# ROM-BANK_004_EAGLE_630.net
KiCad netlist of a schematic drawn in EAGLE
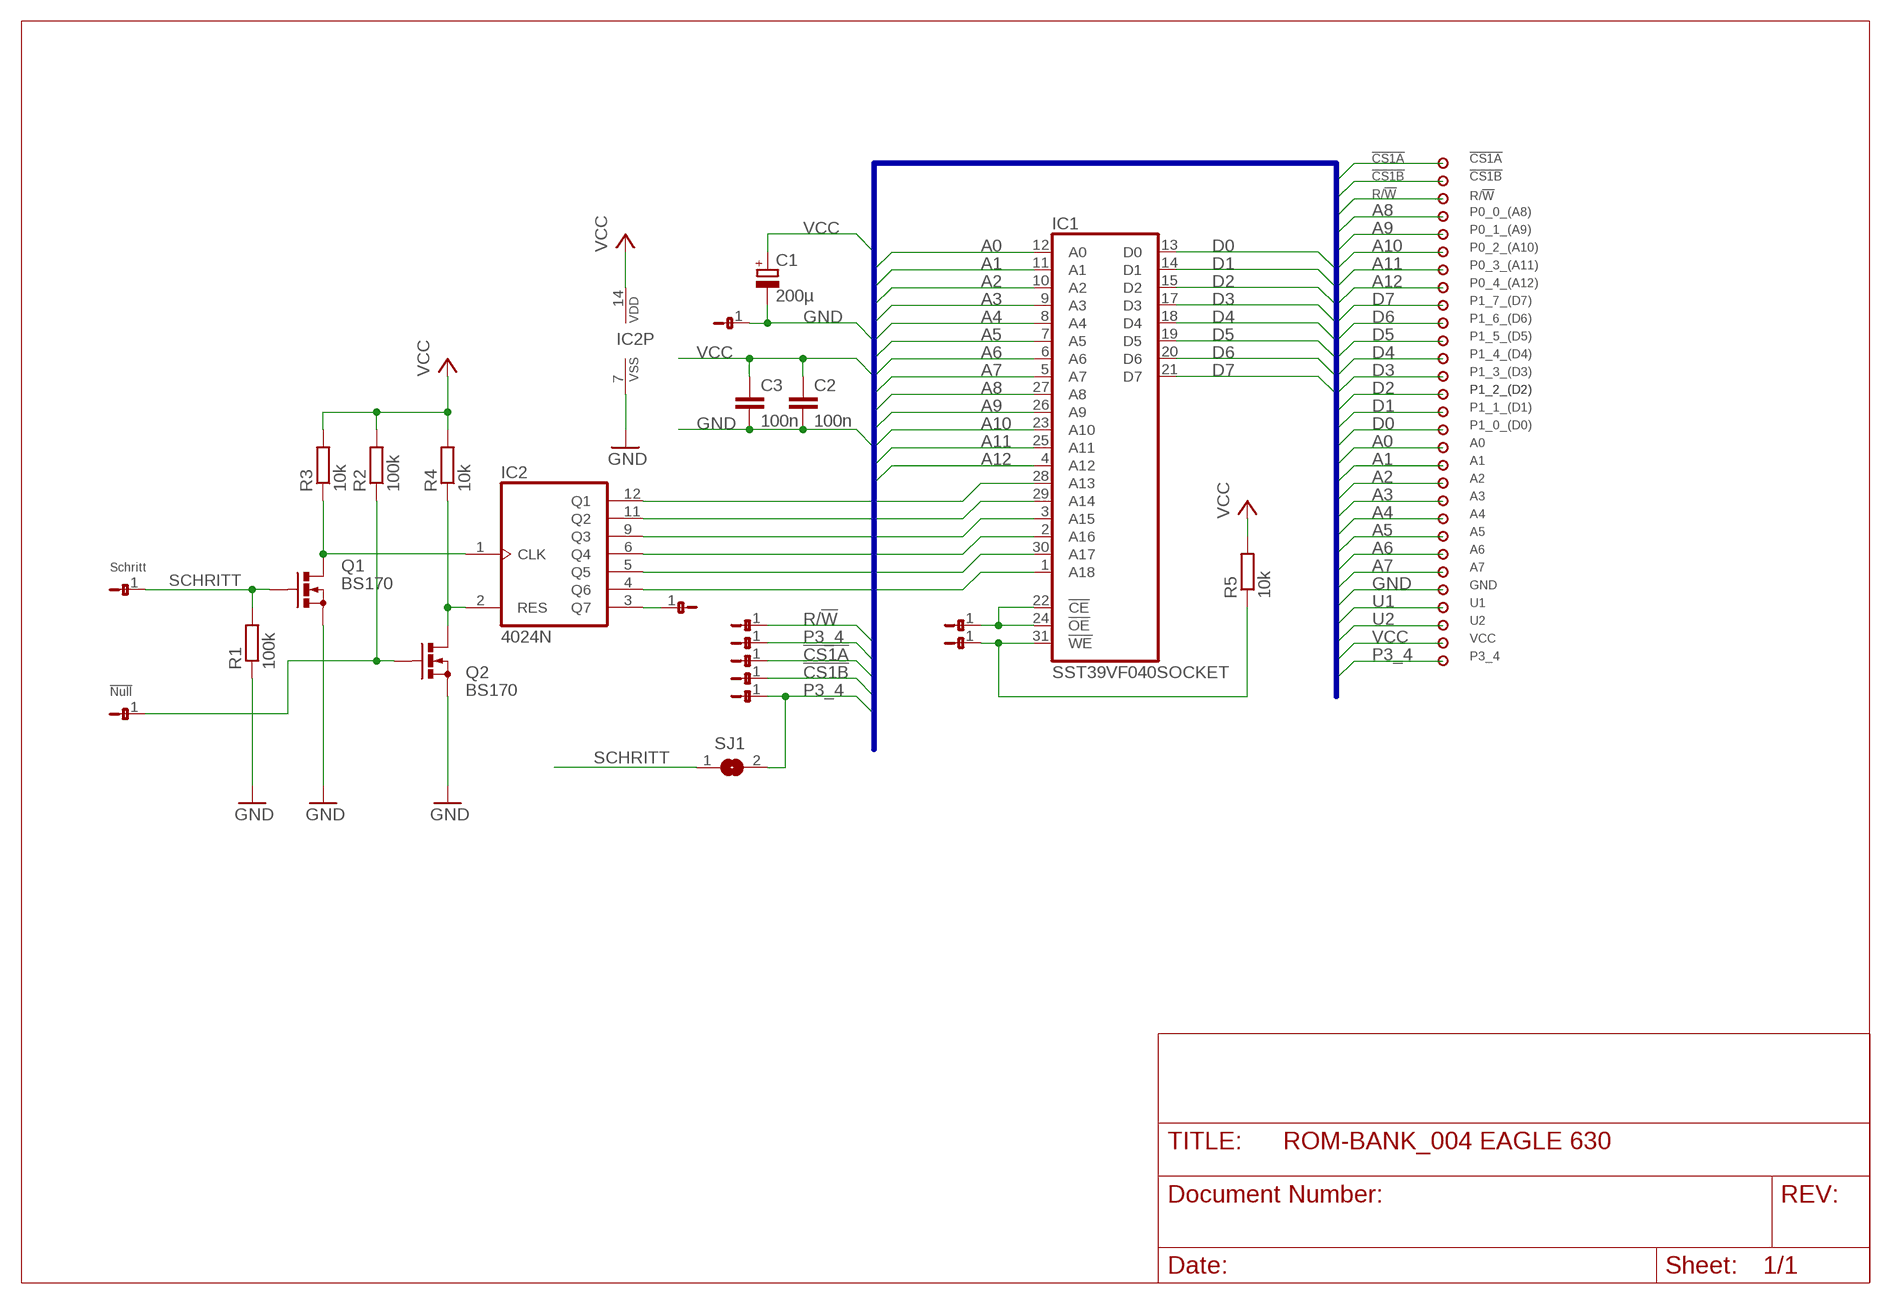
[diagram p0: schematic, sheet 1]

(export (version "E")
  (design (tool "Eeschema 10.0.6"))
  (components
    (comp (ref "!NULL")
      (value "JP1-1JP1-1B")
      (footprint "eagle-import:JP1-1B")
      (libsource (lib "eagle-import") (part "JP1-1JP1-1B"))
    )
    (comp (ref "C1")
      (value "200µ")
      (footprint "eagle-import:E15-6")
      (libsource (lib "eagle-import") (part "CPOL-EUE15-6AXIAL"))
    )
    (comp (ref "C2")
      (value "100n")
      (footprint "eagle-import:C025-024X044")
      (libsource (lib "eagle-import") (part "C-EU025-024X044"))
    )
    (comp (ref "C3")
      (value "100n")
      (footprint "eagle-import:C025-024X044")
      (libsource (lib "eagle-import") (part "C-EU025-024X044"))
    )
    (comp (ref "IC1")
      (value "SST39VF040SOCKET")
      (footprint "eagle-import:PLCC-32-SOCKET")
      (libsource (lib "eagle-import") (part "SST39VF040SOCKET"))
    )
    (comp (ref "IC2")
      (value "4024N")
      (footprint "eagle-import:DIL14")
      (libsource (lib "eagle-import") (part "4024N"))
    )
    (comp (ref "Q1")
      (value "BS170")
      (footprint "eagle-import:SOT54E")
      (libsource (lib "eagle-import") (part "BS170"))
    )
    (comp (ref "Q2")
      (value "BS170")
      (footprint "eagle-import:SOT54E")
      (libsource (lib "eagle-import") (part "BS170"))
    )
    (comp (ref "Q7")
      (value "JP1-1JP1-1B")
      (footprint "eagle-import:JP1-1B")
      (libsource (lib "eagle-import") (part "JP1-1JP1-1B"))
    )
    (comp (ref "R/!W")
      (value "JP1-1JP1-1B")
      (footprint "eagle-import:JP1-1B")
      (libsource (lib "eagle-import") (part "JP1-1JP1-1B"))
    )
    (comp (ref "R1")
      (value "100k")
      (footprint "eagle-import:0207_10")
      (libsource (lib "eagle-import") (part "R-EU_0207/10"))
    )
    (comp (ref "R2")
      (value "100k")
      (footprint "eagle-import:0207_10")
      (libsource (lib "eagle-import") (part "R-EU_0207/10"))
    )
    (comp (ref "R3")
      (value "10k")
      (footprint "eagle-import:0207_10")
      (libsource (lib "eagle-import") (part "R-EU_0207/10"))
    )
    (comp (ref "R4")
      (value "10k")
      (footprint "eagle-import:0207_10")
      (libsource (lib "eagle-import") (part "R-EU_0207/10"))
    )
    (comp (ref "R5")
      (value "10k")
      (footprint "eagle-import:0207_10")
      (libsource (lib "eagle-import") (part "R-EU_0207/10"))
    )
    (comp (ref "SCHRITT")
      (value "JP1-1JP1-1B")
      (footprint "eagle-import:JP1-1B")
      (libsource (lib "eagle-import") (part "JP1-1JP1-1B"))
    )
    (comp (ref "SJ1") (value "SJ") (footprint "eagle-import:SJ") (libsource (lib "eagle-import") (part "SJ")))
    (comp (ref "U$1")
      (value "BUS2929PUR")
      (footprint "eagle-import:BUS29_PUR")
      (libsource (lib "eagle-import") (part "BUS2929PUR"))
    )
    (comp (ref "U$2")
      (value "JP1-1JP1-1B")
      (footprint "eagle-import:JP1-1B")
      (libsource (lib "eagle-import") (part "JP1-1JP1-1B"))
    )
    (comp (ref "U$3")
      (value "JP1-1JP1-1B")
      (footprint "eagle-import:JP1-1B")
      (libsource (lib "eagle-import") (part "JP1-1JP1-1B"))
    )
    (comp (ref "U$4")
      (value "JP1-1JP1-1B")
      (footprint "eagle-import:JP1-1B")
      (libsource (lib "eagle-import") (part "JP1-1JP1-1B"))
    )
    (comp (ref "U$6")
      (value "JP1-1JP1-1B")
      (footprint "eagle-import:JP1-1B")
      (libsource (lib "eagle-import") (part "JP1-1JP1-1B"))
    )
    (comp (ref "U$8")
      (value "JP1-1JP1-1B")
      (footprint "eagle-import:JP1-1B")
      (libsource (lib "eagle-import") (part "JP1-1JP1-1B"))
    )
    (comp (ref "U$9")
      (value "JP1-1JP1-1B")
      (footprint "eagle-import:JP1-1B")
      (libsource (lib "eagle-import") (part "JP1-1JP1-1B"))
    )
    (comp (ref "U$10")
      (value "JP1-1JP1-1B")
      (footprint "eagle-import:JP1-1B")
      (libsource (lib "eagle-import") (part "JP1-1JP1-1B"))
    )
  )
  (nets
    (net (code "1") (name "/A0") (class "Default")
      (node (ref "IC1") (pin "12") (pinfunction "A0_12") (pintype "input"))
      (node (ref "U$1") (pin "1.13") (pinfunction "P$13_1.13") (pintype "bidirectional"))
    )
    (net (code "2") (name "/A1") (class "Default")
      (node (ref "IC1") (pin "11") (pinfunction "A1_11") (pintype "input"))
      (node (ref "U$1") (pin "1.12") (pinfunction "P$12_1.12") (pintype "bidirectional"))
    )
    (net (code "3") (name "/A2") (class "Default")
      (node (ref "IC1") (pin "10") (pinfunction "A2_10") (pintype "input"))
      (node (ref "U$1") (pin "1.11") (pinfunction "P$11_1.11") (pintype "bidirectional"))
    )
    (net (code "4") (name "/A3") (class "Default")
      (node (ref "IC1") (pin "9") (pinfunction "A3_9") (pintype "input"))
      (node (ref "U$1") (pin "1.10") (pinfunction "P$10_1.10") (pintype "bidirectional"))
    )
    (net (code "5") (name "/A4") (class "Default")
      (node (ref "IC1") (pin "8") (pinfunction "A4_8") (pintype "input"))
      (node (ref "U$1") (pin "1.9") (pinfunction "P$9_1.9") (pintype "bidirectional"))
    )
    (net (code "6") (name "/A5") (class "Default")
      (node (ref "IC1") (pin "7") (pinfunction "A5_7") (pintype "input"))
      (node (ref "U$1") (pin "1.8") (pinfunction "P$8_1.8") (pintype "bidirectional"))
    )
    (net (code "7") (name "/A6") (class "Default")
      (node (ref "IC1") (pin "6") (pinfunction "A6_6") (pintype "input"))
      (node (ref "U$1") (pin "1.7") (pinfunction "P$7_1.7") (pintype "bidirectional"))
    )
    (net (code "8") (name "/A7") (class "Default")
      (node (ref "IC1") (pin "5") (pinfunction "A7_5") (pintype "input"))
      (node (ref "U$1") (pin "1.6") (pinfunction "P$6_1.6") (pintype "bidirectional"))
    )
    (net (code "9") (name "/A8") (class "Default")
      (node (ref "IC1") (pin "27") (pinfunction "A8_27") (pintype "input"))
      (node (ref "U$1") (pin "1.26") (pinfunction "P$26_1.26") (pintype "bidirectional"))
    )
    (net (code "10") (name "/A9") (class "Default")
      (node (ref "IC1") (pin "26") (pinfunction "A9_26") (pintype "input"))
      (node (ref "U$1") (pin "1.25") (pinfunction "P$25_1.25") (pintype "bidirectional"))
    )
    (net (code "11") (name "/A10") (class "Default")
      (node (ref "IC1") (pin "23") (pinfunction "A10_23") (pintype "input"))
      (node (ref "U$1") (pin "1.24") (pinfunction "P$24_1.24") (pintype "bidirectional"))
    )
    (net (code "12") (name "/A11") (class "Default")
      (node (ref "IC1") (pin "25") (pinfunction "A11_25") (pintype "input"))
      (node (ref "U$1") (pin "1.23") (pinfunction "P$23_1.23") (pintype "bidirectional"))
    )
    (net (code "13") (name "/A12") (class "Default")
      (node (ref "IC1") (pin "4") (pinfunction "A12_4") (pintype "input"))
      (node (ref "U$1") (pin "1.22") (pinfunction "P$22_1.22") (pintype "bidirectional"))
    )
    (net (code "14") (name "/D0") (class "Default")
      (node (ref "IC1") (pin "13") (pinfunction "D0_13") (pintype "bidirectional"))
      (node (ref "U$1") (pin "1.14") (pinfunction "P$14_1.14") (pintype "bidirectional"))
    )
    (net (code "15") (name "/D1") (class "Default")
      (node (ref "IC1") (pin "14") (pinfunction "D1_14") (pintype "bidirectional"))
      (node (ref "U$1") (pin "1.15") (pinfunction "P$15_1.15") (pintype "bidirectional"))
    )
    (net (code "16") (name "/D2") (class "Default")
      (node (ref "IC1") (pin "15") (pinfunction "D2_15") (pintype "bidirectional"))
      (node (ref "U$1") (pin "1.16") (pinfunction "P$16_1.16") (pintype "bidirectional"))
    )
    (net (code "17") (name "/D3") (class "Default")
      (node (ref "IC1") (pin "17") (pinfunction "D3_17") (pintype "bidirectional"))
      (node (ref "U$1") (pin "1.17") (pinfunction "P$17_1.17") (pintype "bidirectional"))
    )
    (net (code "18") (name "/D4") (class "Default")
      (node (ref "IC1") (pin "18") (pinfunction "D4_18") (pintype "bidirectional"))
      (node (ref "U$1") (pin "1.18") (pinfunction "P$18_1.18") (pintype "bidirectional"))
    )
    (net (code "19") (name "/D5") (class "Default")
      (node (ref "IC1") (pin "19") (pinfunction "D5_19") (pintype "bidirectional"))
      (node (ref "U$1") (pin "1.19") (pinfunction "P$19_1.19") (pintype "bidirectional"))
    )
    (net (code "20") (name "/D6") (class "Default")
      (node (ref "IC1") (pin "20") (pinfunction "D6_20") (pintype "bidirectional"))
      (node (ref "U$1") (pin "1.20") (pinfunction "P$20_1.20") (pintype "bidirectional"))
    )
    (net (code "21") (name "/D7") (class "Default")
      (node (ref "IC1") (pin "21") (pinfunction "D7_21") (pintype "bidirectional"))
      (node (ref "U$1") (pin "1.21") (pinfunction "P$21_1.21") (pintype "bidirectional"))
    )
    (net (code "35") (name "/P3_4") (class "Default")
      (node (ref "SJ1") (pin "2") (pinfunction "2_2") (pintype "passive"))
      (node (ref "U$1") (pin "1.1") (pinfunction "P$1_1.1") (pintype "bidirectional"))
      (node (ref "U$3") (pin "1") (pinfunction "1_1") (pintype "passive"))
      (node (ref "U$6") (pin "1") (pinfunction "1_1") (pintype "passive"))
    )
    (net (code "36") (name "/R{slash}~{W}") (class "Default")
      (node (ref "R/!W") (pin "1") (pinfunction "1_1") (pintype "passive"))
      (node (ref "U$1") (pin "1.27") (pinfunction "P$27_1.27") (pintype "bidirectional"))
    )
    (net (code "37") (name "/SCHRITT") (class "Default")
      (node (ref "Q1") (pin "G") (pinfunction "G_G") (pintype "passive"))
      (node (ref "R1") (pin "2") (pinfunction "2_2") (pintype "passive"))
      (node (ref "SCHRITT") (pin "1") (pinfunction "1_1") (pintype "passive"))
      (node (ref "SJ1") (pin "1") (pinfunction "1_1") (pintype "passive"))
    )
    (net (code "38") (name "/U1") (class "Default")
      (node (ref "U$1") (pin "1.4") (pinfunction "P$4_1.4") (pintype "bidirectional"))
    )
    (net (code "39") (name "/U2") (class "Default")
      (node (ref "U$1") (pin "1.3") (pinfunction "P$3_1.3") (pintype "bidirectional"))
    )
    (net (code "40") (name "/~{CS1A}") (class "Default")
      (node (ref "U$1") (pin "1.29") (pinfunction "P$29_1.29") (pintype "bidirectional"))
      (node (ref "U$8") (pin "1") (pinfunction "1_1") (pintype "passive"))
    )
    (net (code "41") (name "/~{CS1B}") (class "Default")
      (node (ref "U$1") (pin "1.28") (pinfunction "P$28_1.28") (pintype "bidirectional"))
      (node (ref "U$9") (pin "1") (pinfunction "1_1") (pintype "passive"))
    )
    (net (code "42") (name "GND") (class "Default")
      (node (ref "C1") (pin "-") (pinfunction "-_-") (pintype "passive"))
      (node (ref "C2") (pin "2") (pinfunction "2_2") (pintype "passive"))
      (node (ref "C3") (pin "2") (pinfunction "2_2") (pintype "passive"))
      (node (ref "IC2") (pin "7") (pinfunction "VSS_7") (pintype "power_in"))
      (node (ref "Q1") (pin "S") (pinfunction "S_S") (pintype "passive"))
      (node (ref "Q2") (pin "S") (pinfunction "S_S") (pintype "passive"))
      (node (ref "R1") (pin "1") (pinfunction "1_1") (pintype "passive"))
      (node (ref "U$1") (pin "1.5") (pinfunction "P$5_1.5") (pintype "bidirectional"))
      (node (ref "U$2") (pin "1") (pinfunction "1_1") (pintype "passive"))
    )
    (net (code "43") (name "Net-(!NULL-Pad1)") (class "Default")
      (node (ref "!NULL") (pin "1") (pinfunction "1_1") (pintype "passive"))
      (node (ref "Q2") (pin "G") (pinfunction "G_G") (pintype "passive"))
      (node (ref "R2") (pin "1") (pinfunction "1_1") (pintype "passive"))
    )
    (net (code "44") (name "Net-(IC1A-A13)") (class "Default")
      (node (ref "IC1") (pin "28") (pinfunction "A13_28") (pintype "input"))
      (node (ref "IC2") (pin "12") (pinfunction "Q1_12") (pintype "output"))
    )
    (net (code "45") (name "Net-(IC1A-A14)") (class "Default")
      (node (ref "IC1") (pin "29") (pinfunction "A14_29") (pintype "input"))
      (node (ref "IC2") (pin "11") (pinfunction "Q2_11") (pintype "output"))
    )
    (net (code "46") (name "Net-(IC1A-A15)") (class "Default")
      (node (ref "IC1") (pin "3") (pinfunction "A15_3") (pintype "input"))
      (node (ref "IC2") (pin "9") (pinfunction "Q3_9") (pintype "output"))
    )
    (net (code "47") (name "Net-(IC1A-A16)") (class "Default")
      (node (ref "IC1") (pin "2") (pinfunction "A16_2") (pintype "input"))
      (node (ref "IC2") (pin "6") (pinfunction "Q4_6") (pintype "output"))
    )
    (net (code "48") (name "Net-(IC1A-A17)") (class "Default")
      (node (ref "IC1") (pin "30") (pinfunction "A17_30") (pintype "input"))
      (node (ref "IC2") (pin "5") (pinfunction "Q5_5") (pintype "output"))
    )
    (net (code "49") (name "Net-(IC1A-A18)") (class "Default")
      (node (ref "IC1") (pin "1") (pinfunction "A18_1") (pintype "input"))
      (node (ref "IC2") (pin "4") (pinfunction "Q6_4") (pintype "output"))
    )
    (net (code "50") (name "Net-(IC1A-~{CE})") (class "Default")
      (node (ref "IC1") (pin "22") (pinfunction "~{CE}_22") (pintype "input"))
      (node (ref "IC1") (pin "24") (pinfunction "~{OE}_24") (pintype "input"))
      (node (ref "U$10") (pin "1") (pinfunction "1_1") (pintype "passive"))
    )
    (net (code "51") (name "Net-(IC1A-~{WE})") (class "Default")
      (node (ref "IC1") (pin "31") (pinfunction "~{WE}_31") (pintype "input"))
      (node (ref "R5") (pin "1") (pinfunction "1_1") (pintype "passive"))
      (node (ref "U$4") (pin "1") (pinfunction "1_1") (pintype "passive"))
    )
    (net (code "52") (name "Net-(IC2A-CLK)") (class "Default")
      (node (ref "IC2") (pin "1") (pinfunction "CLK_1") (pintype "input"))
      (node (ref "Q1") (pin "D") (pinfunction "D_D") (pintype "passive"))
      (node (ref "R3") (pin "1") (pinfunction "1_1") (pintype "passive"))
    )
    (net (code "53") (name "Net-(IC2A-Q7)") (class "Default")
      (node (ref "IC2") (pin "3") (pinfunction "Q7_3") (pintype "output"))
      (node (ref "Q7") (pin "1") (pinfunction "1_1") (pintype "passive"))
    )
    (net (code "54") (name "Net-(IC2A-RES)") (class "Default")
      (node (ref "IC2") (pin "2") (pinfunction "RES_2") (pintype "input"))
      (node (ref "Q2") (pin "D") (pinfunction "D_D") (pintype "passive"))
      (node (ref "R4") (pin "1") (pinfunction "1_1") (pintype "passive"))
    )
    (net (code "55") (name "VCC") (class "Default")
      (node (ref "C1") (pin "+") (pinfunction "+_+") (pintype "passive"))
      (node (ref "C2") (pin "1") (pinfunction "1_1") (pintype "passive"))
      (node (ref "C3") (pin "1") (pinfunction "1_1") (pintype "passive"))
      (node (ref "IC2") (pin "14") (pinfunction "VDD_14") (pintype "power_in"))
      (node (ref "R2") (pin "2") (pinfunction "2_2") (pintype "passive"))
      (node (ref "R3") (pin "2") (pinfunction "2_2") (pintype "passive"))
      (node (ref "R4") (pin "2") (pinfunction "2_2") (pintype "passive"))
      (node (ref "R5") (pin "2") (pinfunction "2_2") (pintype "passive"))
      (node (ref "U$1") (pin "1.2") (pinfunction "P$2_1.2") (pintype "bidirectional"))
    )
  )
)
